# Sheet_Project_Batteries_V2.net
KiCad netlist of a schematic drawn in Altium Designer
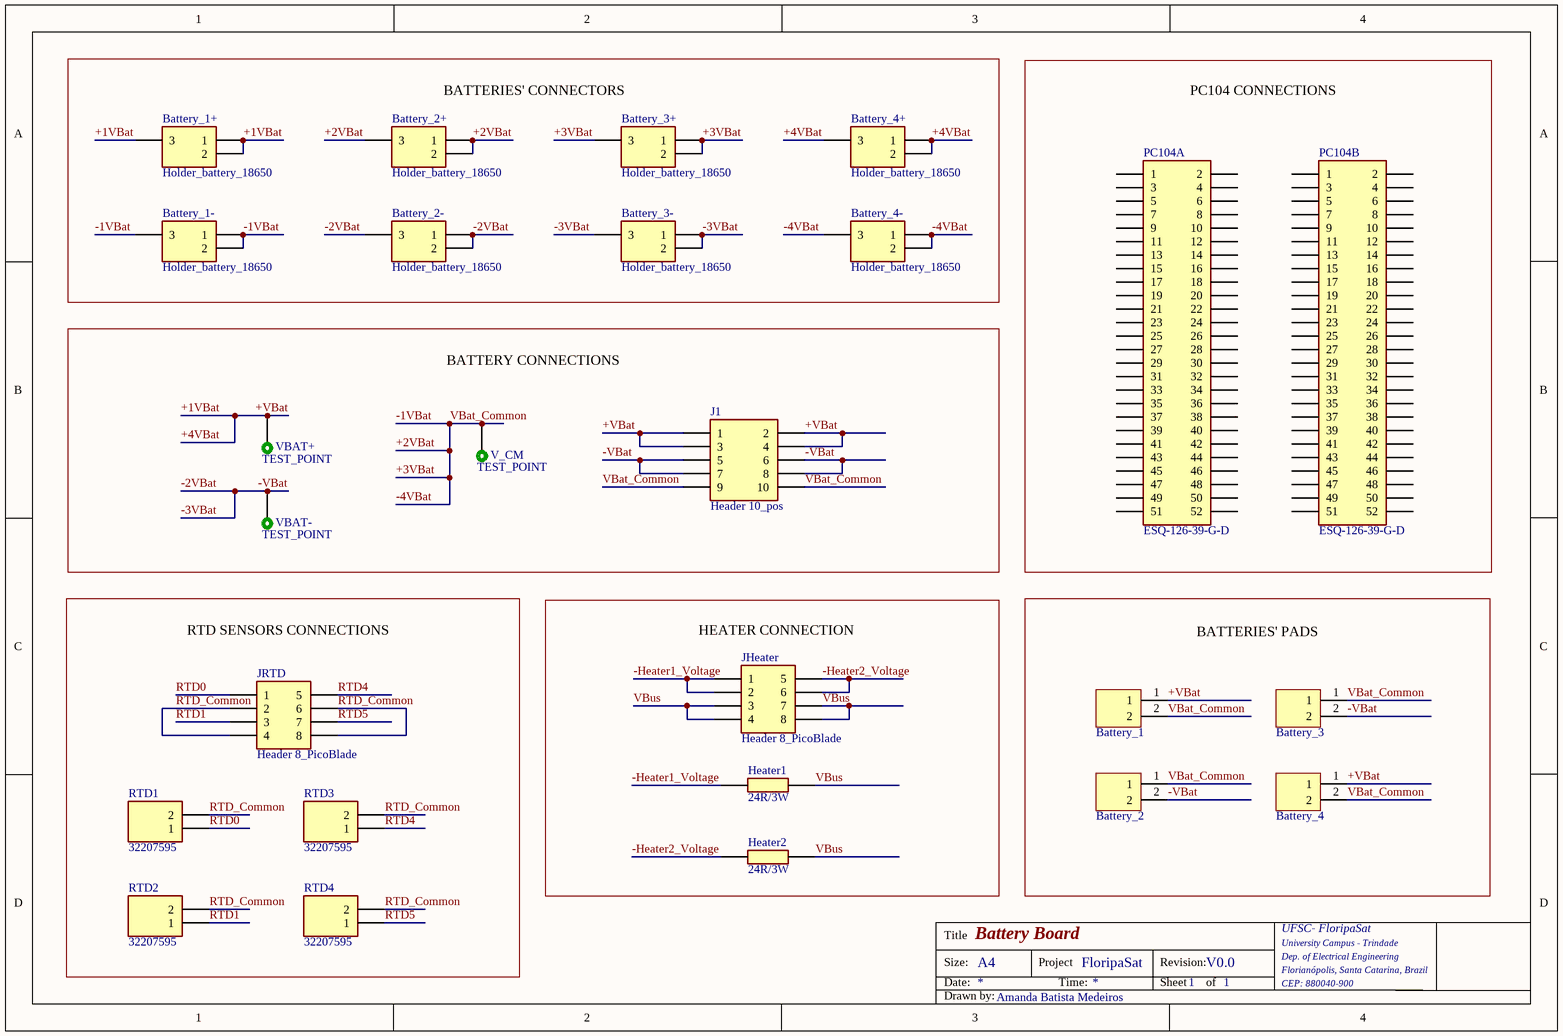
[diagram p0: Sheet_Project_Batteries_V2.SchDoc]

(export (version "E")
  (design (tool "Eeschema 10.0.6"))
  (components
    (comp (ref "Battery_1")
      (value "BATTERY")
      (footprint "BATTERY")
      (description "Battery Pads")
      (libsource (lib "Battery_V2") (part "BATTERY"))
    )
    (comp (ref "Battery_1+")
      (value "Holder_battery_18650")
      (footprint "54")
      (description "Cylindrical Battery Contacts, Clips, Holders & Springs 16-19mm PC BATTERY CLIP")
      (fields (field (name "MANUFACTURER_PART_NUMBER") "54") (field (name "MOUSER PART NUMBER") "534-54"))
      (libsource (lib "*") (part "54"))
    )
    (comp (ref "Battery_1-")
      (value "Holder_battery_18650")
      (footprint "54")
      (description "Cylindrical Battery Contacts, Clips, Holders & Springs 16-19mm PC BATTERY CLIP")
      (fields (field (name "MANUFACTURER_PART_NUMBER") "54") (field (name "MOUSER PART NUMBER") "534-54"))
      (libsource (lib "*") (part "54"))
    )
    (comp (ref "Battery_2")
      (value "BATTERY")
      (footprint "BATTERY")
      (description "Battery Pads")
      (libsource (lib "Battery_V2") (part "BATTERY"))
    )
    (comp (ref "Battery_2+")
      (value "Holder_battery_18650")
      (footprint "54")
      (description "Cylindrical Battery Contacts, Clips, Holders & Springs 16-19mm PC BATTERY CLIP")
      (fields (field (name "MANUFACTURER_PART_NUMBER") "54") (field (name "MOUSER PART NUMBER") "534-54"))
      (libsource (lib "*") (part "54"))
    )
    (comp (ref "Battery_2-")
      (value "Holder_battery_18650")
      (footprint "54")
      (description "Cylindrical Battery Contacts, Clips, Holders & Springs 16-19mm PC BATTERY CLIP")
      (fields (field (name "MANUFACTURER_PART_NUMBER") "54") (field (name "MOUSER PART NUMBER") "534-54"))
      (libsource (lib "*") (part "54"))
    )
    (comp (ref "Battery_3")
      (value "BATTERY")
      (footprint "BATTERY")
      (description "Battery Pads")
      (libsource (lib "Battery_V2") (part "BATTERY"))
    )
    (comp (ref "Battery_3+")
      (value "Holder_battery_18650")
      (footprint "54")
      (description "Cylindrical Battery Contacts, Clips, Holders & Springs 16-19mm PC BATTERY CLIP")
      (fields (field (name "MANUFACTURER_PART_NUMBER") "54") (field (name "MOUSER PART NUMBER") "534-54"))
      (libsource (lib "*") (part "54"))
    )
    (comp (ref "Battery_3-")
      (value "Holder_battery_18650")
      (footprint "54")
      (description "Cylindrical Battery Contacts, Clips, Holders & Springs 16-19mm PC BATTERY CLIP")
      (fields (field (name "MANUFACTURER_PART_NUMBER") "54") (field (name "MOUSER PART NUMBER") "534-54"))
      (libsource (lib "*") (part "54"))
    )
    (comp (ref "Battery_4")
      (value "BATTERY")
      (footprint "BATTERY")
      (description "Battery Pads")
      (libsource (lib "Battery_V2") (part "BATTERY"))
    )
    (comp (ref "Battery_4+")
      (value "Holder_battery_18650")
      (footprint "54")
      (description "Cylindrical Battery Contacts, Clips, Holders & Springs 16-19mm PC BATTERY CLIP")
      (fields (field (name "MANUFACTURER_PART_NUMBER") "54") (field (name "MOUSER PART NUMBER") "534-54"))
      (libsource (lib "*") (part "54"))
    )
    (comp (ref "Battery_4-")
      (value "Holder_battery_18650")
      (footprint "54")
      (description "Cylindrical Battery Contacts, Clips, Holders & Springs 16-19mm PC BATTERY CLIP")
      (fields (field (name "MANUFACTURER_PART_NUMBER") "54") (field (name "MOUSER PART NUMBER") "534-54"))
      (libsource (lib "*") (part "54"))
    )
    (comp (ref "Heater1")
      (value "24R/3W")
      (footprint "RESAD3322W86L1422D475")
      (description "Wirewound Resistors - Through Hole 3watts 24ohms 1%")
      (fields (field (name "MANUFACTURER_PART_NUMBER") "RS02B24R00FE12"))
      (libsource (lib "*") (part "RS02B24R00FE12"))
    )
    (comp (ref "Heater2")
      (value "24R/3W")
      (footprint "RESAD3322W86L1422D475")
      (description "Wirewound Resistors - Through Hole 3watts 24ohms 1%")
      (fields (field (name "MANUFACTURER_PART_NUMBER") "RS02B24R00FE12"))
      (libsource (lib "*") (part "RS02B24R00FE12"))
    )
    (comp (ref "J1")
      (value "Header 10_pos")
      (footprint "HDRV10W64P254_2X5_1270X502X521P")
      (description "Headers & Wire Housings .100\" Terminal Strip")
      (fields
        (field (name "MANUFACTURER_PART_NUMBER") "TSW-105-05-G-D")
        (field (name "MOUSER PART NUMBER") "200-TSW10505GD")
      )
      (libsource (lib "*") (part "TSW-105-05-G-D"))
    )
    (comp (ref "JHeater")
      (value "Header 8_PicoBlade")
      (footprint "53398-0871")
      (description "Headers & Wire Housings VERTICAL HDR SMT 8P")
      (fields
        (field (name "MOUSER2 PART NUMBER") "538-53398-0871")
        (field (name "MANUFACTURER_PART_NUMBER") "53398-0871")
      )
      (libsource (lib "*") (part "53398-0871"))
    )
    (comp (ref "JRTD")
      (value "Header 8_PicoBlade")
      (footprint "53398-0871")
      (description "Headers & Wire Housings VERTICAL HDR SMT 8P")
      (fields
        (field (name "MOUSER2 PART NUMBER") "538-53398-0871")
        (field (name "MANUFACTURER_PART_NUMBER") "53398-0871")
      )
      (libsource (lib "*") (part "53398-0871"))
    )
    (comp (ref "PC104A")
      (value "ESQ-126-39-G-D")
      (footprint "ESQ-126-Y-X-D")
      (description "PC / 104 Connectors .100\" PC/104 Elevated Socket Strip")
      (fields (field (name "MOUSER PART NUMBER") "200-ESQ12639GD") (field (name "RS PART NUMBER") "1595654"))
      (libsource (lib "*") (part "ESQ-126-39-G-D"))
    )
    (comp (ref "PC104B")
      (value "ESQ-126-39-G-D")
      (footprint "ESQ-126-Y-X-D")
      (description "PC / 104 Connectors .100\" PC/104 Elevated Socket Strip")
      (fields (field (name "MOUSER PART NUMBER") "200-ESQ12639GD") (field (name "RS PART NUMBER") "1595654"))
      (libsource (lib "*") (part "ESQ-126-39-G-D"))
    )
    (comp (ref "RTD1")
      (value "32207595")
      (footprint "THRMC3216X70N")
      (description "Board Mount Temperature Sensors SMD1206(V) Pt 1000 Class B -50 to +130C")
      (libsource (lib "*") (part "32207595"))
    )
    (comp (ref "RTD2")
      (value "32207595")
      (footprint "THRMC3216X70N")
      (description "Board Mount Temperature Sensors SMD1206(V) Pt 1000 Class B -50 to +130C")
      (libsource (lib "*") (part "32207595"))
    )
    (comp (ref "RTD3")
      (value "32207595")
      (footprint "THRMC3216X70N")
      (description "Board Mount Temperature Sensors SMD1206(V) Pt 1000 Class B -50 to +130C")
      (libsource (lib "*") (part "32207595"))
    )
    (comp (ref "RTD4")
      (value "32207595")
      (footprint "THRMC3216X70N")
      (description "Board Mount Temperature Sensors SMD1206(V) Pt 1000 Class B -50 to +130C")
      (libsource (lib "*") (part "32207595"))
    )
    (comp (ref "VBAT+")
      (value "TEST_POINT")
      (footprint "Test_Point")
      (description "Test Point - Headers & Wire Housings .100\" Terminal Strip")
      (libsource (lib "Battery_V2") (part "TEST_POINT"))
    )
    (comp (ref "VBAT-")
      (value "TEST_POINT")
      (footprint "Test_Point")
      (description "Test Point - Headers & Wire Housings .100\" Terminal Strip")
      (libsource (lib "Battery_V2") (part "TEST_POINT"))
    )
    (comp (ref "V_CM")
      (value "TEST_POINT")
      (footprint "Test_Point")
      (description "Test Point - Headers & Wire Housings .100\" Terminal Strip")
      (libsource (lib "Battery_V2") (part "TEST_POINT"))
    )
  )
  (nets
    (net (code "1") (name "/+1VBat") (class "Default")
      (node (ref "Battery_1") (pin "1") (pinfunction "1_1") (pintype "passive"))
      (node (ref "Battery_1+") (pin "1") (pinfunction "1_1") (pintype "passive"))
      (node (ref "Battery_1+") (pin "2") (pinfunction "2_2") (pintype "passive"))
      (node (ref "Battery_1+") (pin "3") (pinfunction "3_3") (pintype "passive"))
      (node (ref "Battery_4") (pin "1") (pinfunction "1_1") (pintype "passive"))
      (node (ref "Battery_4+") (pin "1") (pinfunction "1_1") (pintype "passive"))
      (node (ref "Battery_4+") (pin "2") (pinfunction "2_2") (pintype "passive"))
      (node (ref "Battery_4+") (pin "3") (pinfunction "3_3") (pintype "passive"))
      (node (ref "J1") (pin "1") (pinfunction "1_1") (pintype "passive"))
      (node (ref "J1") (pin "2") (pinfunction "2_2") (pintype "passive"))
      (node (ref "J1") (pin "3") (pinfunction "3_3") (pintype "passive"))
      (node (ref "J1") (pin "4") (pinfunction "4_4") (pintype "passive"))
      (node (ref "VBAT+") (pin "1") (pinfunction "1_1") (pintype "passive"))
    )
    (net (code "2") (name "/+2VBat") (class "Default")
      (node (ref "Battery_1") (pin "2") (pinfunction "2_2") (pintype "passive"))
      (node (ref "Battery_1-") (pin "1") (pinfunction "1_1") (pintype "passive"))
      (node (ref "Battery_1-") (pin "2") (pinfunction "2_2") (pintype "passive"))
      (node (ref "Battery_1-") (pin "3") (pinfunction "3_3") (pintype "passive"))
      (node (ref "Battery_2") (pin "1") (pinfunction "1_1") (pintype "passive"))
      (node (ref "Battery_2+") (pin "1") (pinfunction "1_1") (pintype "passive"))
      (node (ref "Battery_2+") (pin "2") (pinfunction "2_2") (pintype "passive"))
      (node (ref "Battery_2+") (pin "3") (pinfunction "3_3") (pintype "passive"))
      (node (ref "Battery_3") (pin "1") (pinfunction "1_1") (pintype "passive"))
      (node (ref "Battery_3+") (pin "1") (pinfunction "1_1") (pintype "passive"))
      (node (ref "Battery_3+") (pin "2") (pinfunction "2_2") (pintype "passive"))
      (node (ref "Battery_3+") (pin "3") (pinfunction "3_3") (pintype "passive"))
      (node (ref "Battery_4") (pin "2") (pinfunction "2_2") (pintype "passive"))
      (node (ref "Battery_4-") (pin "1") (pinfunction "1_1") (pintype "passive"))
      (node (ref "Battery_4-") (pin "2") (pinfunction "2_2") (pintype "passive"))
      (node (ref "Battery_4-") (pin "3") (pinfunction "3_3") (pintype "passive"))
      (node (ref "J1") (pin "10") (pinfunction "10_10") (pintype "passive"))
      (node (ref "J1") (pin "9") (pinfunction "9_9") (pintype "passive"))
      (node (ref "V_CM") (pin "1") (pinfunction "1_1") (pintype "passive"))
    )
    (net (code "3") (name "/-2VBat") (class "Default")
      (node (ref "Battery_2") (pin "2") (pinfunction "2_2") (pintype "passive"))
      (node (ref "Battery_2-") (pin "1") (pinfunction "1_1") (pintype "passive"))
      (node (ref "Battery_2-") (pin "2") (pinfunction "2_2") (pintype "passive"))
      (node (ref "Battery_2-") (pin "3") (pinfunction "3_3") (pintype "passive"))
      (node (ref "Battery_3") (pin "2") (pinfunction "2_2") (pintype "passive"))
      (node (ref "Battery_3-") (pin "1") (pinfunction "1_1") (pintype "passive"))
      (node (ref "Battery_3-") (pin "2") (pinfunction "2_2") (pintype "passive"))
      (node (ref "Battery_3-") (pin "3") (pinfunction "3_3") (pintype "passive"))
      (node (ref "J1") (pin "5") (pinfunction "5_5") (pintype "passive"))
      (node (ref "J1") (pin "6") (pinfunction "6_6") (pintype "passive"))
      (node (ref "J1") (pin "7") (pinfunction "7_7") (pintype "passive"))
      (node (ref "J1") (pin "8") (pinfunction "8_8") (pintype "passive"))
      (node (ref "VBAT-") (pin "1") (pinfunction "1_1") (pintype "passive"))
    )
    (net (code "4") (name "/-Heater1_Voltage") (class "Default")
      (node (ref "Heater1") (pin "1") (pinfunction "1_1") (pintype "passive"))
      (node (ref "JHeater") (pin "1") (pinfunction "1_1") (pintype "passive"))
      (node (ref "JHeater") (pin "2") (pinfunction "2_2") (pintype "passive"))
    )
    (net (code "5") (name "/-Heater2_Voltage") (class "Default")
      (node (ref "Heater2") (pin "1") (pinfunction "1_1") (pintype "passive"))
      (node (ref "JHeater") (pin "5") (pinfunction "5_5") (pintype "passive"))
      (node (ref "JHeater") (pin "6") (pinfunction "6_6") (pintype "passive"))
    )
    (net (code "6") (name "/RTD0") (class "Default")
      (node (ref "JRTD") (pin "1") (pinfunction "1_1") (pintype "passive"))
      (node (ref "RTD1") (pin "1") (pinfunction "1_1") (pintype "passive"))
    )
    (net (code "7") (name "/RTD1") (class "Default")
      (node (ref "JRTD") (pin "3") (pinfunction "3_3") (pintype "passive"))
      (node (ref "RTD2") (pin "1") (pinfunction "1_1") (pintype "passive"))
    )
    (net (code "8") (name "/RTD4") (class "Default")
      (node (ref "JRTD") (pin "5") (pinfunction "5_5") (pintype "passive"))
      (node (ref "RTD3") (pin "1") (pinfunction "1_1") (pintype "passive"))
    )
    (net (code "9") (name "/RTD5") (class "Default")
      (node (ref "JRTD") (pin "7") (pinfunction "7_7") (pintype "passive"))
      (node (ref "RTD4") (pin "1") (pinfunction "1_1") (pintype "passive"))
    )
    (net (code "10") (name "/RTD_Common") (class "Default")
      (node (ref "JRTD") (pin "2") (pinfunction "2_2") (pintype "passive"))
      (node (ref "JRTD") (pin "4") (pinfunction "4_4") (pintype "passive"))
      (node (ref "JRTD") (pin "6") (pinfunction "6_6") (pintype "passive"))
      (node (ref "JRTD") (pin "8") (pinfunction "8_8") (pintype "passive"))
      (node (ref "RTD1") (pin "2") (pinfunction "2_2") (pintype "passive"))
      (node (ref "RTD2") (pin "2") (pinfunction "2_2") (pintype "passive"))
      (node (ref "RTD3") (pin "2") (pinfunction "2_2") (pintype "passive"))
      (node (ref "RTD4") (pin "2") (pinfunction "2_2") (pintype "passive"))
    )
    (net (code "11") (name "/VBus") (class "Default")
      (node (ref "Heater1") (pin "2") (pinfunction "2_2") (pintype "passive"))
      (node (ref "Heater2") (pin "2") (pinfunction "2_2") (pintype "passive"))
      (node (ref "JHeater") (pin "3") (pinfunction "3_3") (pintype "passive"))
      (node (ref "JHeater") (pin "4") (pinfunction "4_4") (pintype "passive"))
      (node (ref "JHeater") (pin "7") (pinfunction "7_7") (pintype "passive"))
      (node (ref "JHeater") (pin "8") (pinfunction "8_8") (pintype "passive"))
    )
    (net (code "12") (name "unconnected-(PC104A-Pad1)") (class "Default")
      (node (ref "PC104A") (pin "1") (pinfunction "1_1") (pintype "passive"))
    )
    (net (code "13") (name "unconnected-(PC104A-Pad2)") (class "Default")
      (node (ref "PC104A") (pin "2") (pinfunction "2_2") (pintype "passive"))
    )
    (net (code "14") (name "unconnected-(PC104A-Pad3)") (class "Default")
      (node (ref "PC104A") (pin "3") (pinfunction "3_3") (pintype "passive"))
    )
    (net (code "15") (name "unconnected-(PC104A-Pad4)") (class "Default")
      (node (ref "PC104A") (pin "4") (pinfunction "4_4") (pintype "passive"))
    )
    (net (code "16") (name "unconnected-(PC104A-Pad5)") (class "Default")
      (node (ref "PC104A") (pin "5") (pinfunction "5_5") (pintype "passive"))
    )
    (net (code "17") (name "unconnected-(PC104A-Pad6)") (class "Default")
      (node (ref "PC104A") (pin "6") (pinfunction "6_6") (pintype "passive"))
    )
    (net (code "18") (name "unconnected-(PC104A-Pad7)") (class "Default")
      (node (ref "PC104A") (pin "7") (pinfunction "7_7") (pintype "passive"))
    )
    (net (code "19") (name "unconnected-(PC104A-Pad8)") (class "Default")
      (node (ref "PC104A") (pin "8") (pinfunction "8_8") (pintype "passive"))
    )
    (net (code "20") (name "unconnected-(PC104A-Pad9)") (class "Default")
      (node (ref "PC104A") (pin "9") (pinfunction "9_9") (pintype "passive"))
    )
    (net (code "21") (name "unconnected-(PC104A-Pad10)") (class "Default")
      (node (ref "PC104A") (pin "10") (pinfunction "10_10") (pintype "passive"))
    )
    (net (code "22") (name "unconnected-(PC104A-Pad11)") (class "Default")
      (node (ref "PC104A") (pin "11") (pinfunction "11_11") (pintype "passive"))
    )
    (net (code "23") (name "unconnected-(PC104A-Pad12)") (class "Default")
      (node (ref "PC104A") (pin "12") (pinfunction "12_12") (pintype "passive"))
    )
    (net (code "24") (name "unconnected-(PC104A-Pad13)") (class "Default")
      (node (ref "PC104A") (pin "13") (pinfunction "13_13") (pintype "passive"))
    )
    (net (code "25") (name "unconnected-(PC104A-Pad14)") (class "Default")
      (node (ref "PC104A") (pin "14") (pinfunction "14_14") (pintype "passive"))
    )
    (net (code "26") (name "unconnected-(PC104A-Pad15)") (class "Default")
      (node (ref "PC104A") (pin "15") (pinfunction "15_15") (pintype "passive"))
    )
    (net (code "27") (name "unconnected-(PC104A-Pad16)") (class "Default")
      (node (ref "PC104A") (pin "16") (pinfunction "16_16") (pintype "passive"))
    )
    (net (code "28") (name "unconnected-(PC104A-Pad17)") (class "Default")
      (node (ref "PC104A") (pin "17") (pinfunction "17_17") (pintype "passive"))
    )
    (net (code "29") (name "unconnected-(PC104A-Pad18)") (class "Default")
      (node (ref "PC104A") (pin "18") (pinfunction "18_18") (pintype "passive"))
    )
    (net (code "30") (name "unconnected-(PC104A-Pad19)") (class "Default")
      (node (ref "PC104A") (pin "19") (pinfunction "19_19") (pintype "passive"))
    )
    (net (code "31") (name "unconnected-(PC104A-Pad20)") (class "Default")
      (node (ref "PC104A") (pin "20") (pinfunction "20_20") (pintype "passive"))
    )
    (net (code "32") (name "unconnected-(PC104A-Pad21)") (class "Default")
      (node (ref "PC104A") (pin "21") (pinfunction "21_21") (pintype "passive"))
    )
    (net (code "33") (name "unconnected-(PC104A-Pad22)") (class "Default")
      (node (ref "PC104A") (pin "22") (pinfunction "22_22") (pintype "passive"))
    )
    (net (code "34") (name "unconnected-(PC104A-Pad23)") (class "Default")
      (node (ref "PC104A") (pin "23") (pinfunction "23_23") (pintype "passive"))
    )
    (net (code "35") (name "unconnected-(PC104A-Pad24)") (class "Default")
      (node (ref "PC104A") (pin "24") (pinfunction "24_24") (pintype "passive"))
    )
    (net (code "36") (name "unconnected-(PC104A-Pad25)") (class "Default")
      (node (ref "PC104A") (pin "25") (pinfunction "25_25") (pintype "passive"))
    )
    (net (code "37") (name "unconnected-(PC104A-Pad26)") (class "Default")
      (node (ref "PC104A") (pin "26") (pinfunction "26_26") (pintype "passive"))
    )
    (net (code "38") (name "unconnected-(PC104A-Pad27)") (class "Default")
      (node (ref "PC104A") (pin "27") (pinfunction "27_27") (pintype "passive"))
    )
    (net (code "39") (name "unconnected-(PC104A-Pad28)") (class "Default")
      (node (ref "PC104A") (pin "28") (pinfunction "28_28") (pintype "passive"))
    )
    (net (code "40") (name "unconnected-(PC104A-Pad29)") (class "Default")
      (node (ref "PC104A") (pin "29") (pinfunction "29_29") (pintype "passive"))
    )
    (net (code "41") (name "unconnected-(PC104A-Pad30)") (class "Default")
      (node (ref "PC104A") (pin "30") (pinfunction "30_30") (pintype "passive"))
    )
    (net (code "42") (name "unconnected-(PC104A-Pad31)") (class "Default")
      (node (ref "PC104A") (pin "31") (pinfunction "31_31") (pintype "passive"))
    )
    (net (code "43") (name "unconnected-(PC104A-Pad32)") (class "Default")
      (node (ref "PC104A") (pin "32") (pinfunction "32_32") (pintype "passive"))
    )
    (net (code "44") (name "unconnected-(PC104A-Pad33)") (class "Default")
      (node (ref "PC104A") (pin "33") (pinfunction "33_33") (pintype "passive"))
    )
    (net (code "45") (name "unconnected-(PC104A-Pad34)") (class "Default")
      (node (ref "PC104A") (pin "34") (pinfunction "34_34") (pintype "passive"))
    )
    (net (code "46") (name "unconnected-(PC104A-Pad35)") (class "Default")
      (node (ref "PC104A") (pin "35") (pinfunction "35_35") (pintype "passive"))
    )
    (net (code "47") (name "unconnected-(PC104A-Pad36)") (class "Default")
      (node (ref "PC104A") (pin "36") (pinfunction "36_36") (pintype "passive"))
    )
    (net (code "48") (name "unconnected-(PC104A-Pad37)") (class "Default")
      (node (ref "PC104A") (pin "37") (pinfunction "37_37") (pintype "passive"))
    )
    (net (code "49") (name "unconnected-(PC104A-Pad38)") (class "Default")
      (node (ref "PC104A") (pin "38") (pinfunction "38_38") (pintype "passive"))
    )
    (net (code "50") (name "unconnected-(PC104A-Pad39)") (class "Default")
      (node (ref "PC104A") (pin "39") (pinfunction "39_39") (pintype "passive"))
    )
    (net (code "51") (name "unconnected-(PC104A-Pad40)") (class "Default")
      (node (ref "PC104A") (pin "40") (pinfunction "40_40") (pintype "passive"))
    )
    (net (code "52") (name "unconnected-(PC104A-Pad41)") (class "Default")
      (node (ref "PC104A") (pin "41") (pinfunction "41_41") (pintype "passive"))
    )
    (net (code "53") (name "unconnected-(PC104A-Pad42)") (class "Default")
      (node (ref "PC104A") (pin "42") (pinfunction "42_42") (pintype "passive"))
    )
    (net (code "54") (name "unconnected-(PC104A-Pad43)") (class "Default")
      (node (ref "PC104A") (pin "43") (pinfunction "43_43") (pintype "passive"))
    )
    (net (code "55") (name "unconnected-(PC104A-Pad44)") (class "Default")
      (node (ref "PC104A") (pin "44") (pinfunction "44_44") (pintype "passive"))
    )
    (net (code "56") (name "unconnected-(PC104A-Pad45)") (class "Default")
      (node (ref "PC104A") (pin "45") (pinfunction "45_45") (pintype "passive"))
    )
    (net (code "57") (name "unconnected-(PC104A-Pad46)") (class "Default")
      (node (ref "PC104A") (pin "46") (pinfunction "46_46") (pintype "passive"))
    )
    (net (code "58") (name "unconnected-(PC104A-Pad47)") (class "Default")
      (node (ref "PC104A") (pin "47") (pinfunction "47_47") (pintype "passive"))
    )
    (net (code "59") (name "unconnected-(PC104A-Pad48)") (class "Default")
      (node (ref "PC104A") (pin "48") (pinfunction "48_48") (pintype "passive"))
    )
    (net (code "60") (name "unconnected-(PC104A-Pad49)") (class "Default")
      (node (ref "PC104A") (pin "49") (pinfunction "49_49") (pintype "passive"))
    )
    (net (code "61") (name "unconnected-(PC104A-Pad50)") (class "Default")
      (node (ref "PC104A") (pin "50") (pinfunction "50_50") (pintype "passive"))
    )
    (net (code "62") (name "unconnected-(PC104A-Pad51)") (class "Default")
      (node (ref "PC104A") (pin "51") (pinfunction "51_51") (pintype "passive"))
    )
    (net (code "63") (name "unconnected-(PC104A-Pad52)") (class "Default")
      (node (ref "PC104A") (pin "52") (pinfunction "52_52") (pintype "passive"))
    )
    (net (code "64") (name "unconnected-(PC104B-Pad1)") (class "Default")
      (node (ref "PC104B") (pin "1") (pinfunction "1_1") (pintype "passive"))
    )
    (net (code "65") (name "unconnected-(PC104B-Pad2)") (class "Default")
      (node (ref "PC104B") (pin "2") (pinfunction "2_2") (pintype "passive"))
    )
    (net (code "66") (name "unconnected-(PC104B-Pad3)") (class "Default")
      (node (ref "PC104B") (pin "3") (pinfunction "3_3") (pintype "passive"))
    )
    (net (code "67") (name "unconnected-(PC104B-Pad4)") (class "Default")
      (node (ref "PC104B") (pin "4") (pinfunction "4_4") (pintype "passive"))
    )
    (net (code "68") (name "unconnected-(PC104B-Pad5)") (class "Default")
      (node (ref "PC104B") (pin "5") (pinfunction "5_5") (pintype "passive"))
    )
    (net (code "69") (name "unconnected-(PC104B-Pad6)") (class "Default")
      (node (ref "PC104B") (pin "6") (pinfunction "6_6") (pintype "passive"))
    )
    (net (code "70") (name "unconnected-(PC104B-Pad7)") (class "Default")
      (node (ref "PC104B") (pin "7") (pinfunction "7_7") (pintype "passive"))
    )
    (net (code "71") (name "unconnected-(PC104B-Pad8)") (class "Default")
      (node (ref "PC104B") (pin "8") (pinfunction "8_8") (pintype "passive"))
    )
    (net (code "72") (name "unconnected-(PC104B-Pad9)") (class "Default")
      (node (ref "PC104B") (pin "9") (pinfunction "9_9") (pintype "passive"))
    )
    (net (code "73") (name "unconnected-(PC104B-Pad10)") (class "Default")
      (node (ref "PC104B") (pin "10") (pinfunction "10_10") (pintype "passive"))
    )
    (net (code "74") (name "unconnected-(PC104B-Pad11)") (class "Default")
      (node (ref "PC104B") (pin "11") (pinfunction "11_11") (pintype "passive"))
    )
    (net (code "75") (name "unconnected-(PC104B-Pad12)") (class "Default")
      (node (ref "PC104B") (pin "12") (pinfunction "12_12") (pintype "passive"))
    )
    (net (code "76") (name "unconnected-(PC104B-Pad13)") (class "Default")
      (node (ref "PC104B") (pin "13") (pinfunction "13_13") (pintype "passive"))
    )
    (net (code "77") (name "unconnected-(PC104B-Pad14)") (class "Default")
      (node (ref "PC104B") (pin "14") (pinfunction "14_14") (pintype "passive"))
    )
    (net (code "78") (name "unconnected-(PC104B-Pad15)") (class "Default")
      (node (ref "PC104B") (pin "15") (pinfunction "15_15") (pintype "passive"))
    )
    (net (code "79") (name "unconnected-(PC104B-Pad16)") (class "Default")
      (node (ref "PC104B") (pin "16") (pinfunction "16_16") (pintype "passive"))
    )
    (net (code "80") (name "unconnected-(PC104B-Pad17)") (class "Default")
      (node (ref "PC104B") (pin "17") (pinfunction "17_17") (pintype "passive"))
    )
    (net (code "81") (name "unconnected-(PC104B-Pad18)") (class "Default")
      (node (ref "PC104B") (pin "18") (pinfunction "18_18") (pintype "passive"))
    )
    (net (code "82") (name "unconnected-(PC104B-Pad19)") (class "Default")
      (node (ref "PC104B") (pin "19") (pinfunction "19_19") (pintype "passive"))
    )
    (net (code "83") (name "unconnected-(PC104B-Pad20)") (class "Default")
      (node (ref "PC104B") (pin "20") (pinfunction "20_20") (pintype "passive"))
    )
    (net (code "84") (name "unconnected-(PC104B-Pad21)") (class "Default")
      (node (ref "PC104B") (pin "21") (pinfunction "21_21") (pintype "passive"))
    )
    (net (code "85") (name "unconnected-(PC104B-Pad22)") (class "Default")
      (node (ref "PC104B") (pin "22") (pinfunction "22_22") (pintype "passive"))
    )
    (net (code "86") (name "unconnected-(PC104B-Pad23)") (class "Default")
      (node (ref "PC104B") (pin "23") (pinfunction "23_23") (pintype "passive"))
    )
    (net (code "87") (name "unconnected-(PC104B-Pad24)") (class "Default")
      (node (ref "PC104B") (pin "24") (pinfunction "24_24") (pintype "passive"))
    )
    (net (code "88") (name "unconnected-(PC104B-Pad25)") (class "Default")
      (node (ref "PC104B") (pin "25") (pinfunction "25_25") (pintype "passive"))
    )
    (net (code "89") (name "unconnected-(PC104B-Pad26)") (class "Default")
      (node (ref "PC104B") (pin "26") (pinfunction "26_26") (pintype "passive"))
    )
    (net (code "90") (name "unconnected-(PC104B-Pad27)") (class "Default")
      (node (ref "PC104B") (pin "27") (pinfunction "27_27") (pintype "passive"))
    )
    (net (code "91") (name "unconnected-(PC104B-Pad28)") (class "Default")
      (node (ref "PC104B") (pin "28") (pinfunction "28_28") (pintype "passive"))
    )
    (net (code "92") (name "unconnected-(PC104B-Pad29)") (class "Default")
      (node (ref "PC104B") (pin "29") (pinfunction "29_29") (pintype "passive"))
    )
    (net (code "93") (name "unconnected-(PC104B-Pad30)") (class "Default")
      (node (ref "PC104B") (pin "30") (pinfunction "30_30") (pintype "passive"))
    )
    (net (code "94") (name "unconnected-(PC104B-Pad31)") (class "Default")
      (node (ref "PC104B") (pin "31") (pinfunction "31_31") (pintype "passive"))
    )
    (net (code "95") (name "unconnected-(PC104B-Pad32)") (class "Default")
      (node (ref "PC104B") (pin "32") (pinfunction "32_32") (pintype "passive"))
    )
    (net (code "96") (name "unconnected-(PC104B-Pad33)") (class "Default")
      (node (ref "PC104B") (pin "33") (pinfunction "33_33") (pintype "passive"))
    )
    (net (code "97") (name "unconnected-(PC104B-Pad34)") (class "Default")
      (node (ref "PC104B") (pin "34") (pinfunction "34_34") (pintype "passive"))
    )
    (net (code "98") (name "unconnected-(PC104B-Pad35)") (class "Default")
      (node (ref "PC104B") (pin "35") (pinfunction "35_35") (pintype "passive"))
    )
    (net (code "99") (name "unconnected-(PC104B-Pad36)") (class "Default")
      (node (ref "PC104B") (pin "36") (pinfunction "36_36") (pintype "passive"))
    )
    (net (code "100") (name "unconnected-(PC104B-Pad37)") (class "Default")
      (node (ref "PC104B") (pin "37") (pinfunction "37_37") (pintype "passive"))
    )
    (net (code "101") (name "unconnected-(PC104B-Pad38)") (class "Default")
      (node (ref "PC104B") (pin "38") (pinfunction "38_38") (pintype "passive"))
    )
    (net (code "102") (name "unconnected-(PC104B-Pad39)") (class "Default")
      (node (ref "PC104B") (pin "39") (pinfunction "39_39") (pintype "passive"))
    )
    (net (code "103") (name "unconnected-(PC104B-Pad40)") (class "Default")
      (node (ref "PC104B") (pin "40") (pinfunction "40_40") (pintype "passive"))
    )
    (net (code "104") (name "unconnected-(PC104B-Pad41)") (class "Default")
      (node (ref "PC104B") (pin "41") (pinfunction "41_41") (pintype "passive"))
    )
    (net (code "105") (name "unconnected-(PC104B-Pad42)") (class "Default")
      (node (ref "PC104B") (pin "42") (pinfunction "42_42") (pintype "passive"))
    )
    (net (code "106") (name "unconnected-(PC104B-Pad43)") (class "Default")
      (node (ref "PC104B") (pin "43") (pinfunction "43_43") (pintype "passive"))
    )
    (net (code "107") (name "unconnected-(PC104B-Pad44)") (class "Default")
      (node (ref "PC104B") (pin "44") (pinfunction "44_44") (pintype "passive"))
    )
    (net (code "108") (name "unconnected-(PC104B-Pad45)") (class "Default")
      (node (ref "PC104B") (pin "45") (pinfunction "45_45") (pintype "passive"))
    )
    (net (code "109") (name "unconnected-(PC104B-Pad46)") (class "Default")
      (node (ref "PC104B") (pin "46") (pinfunction "46_46") (pintype "passive"))
    )
    (net (code "110") (name "unconnected-(PC104B-Pad47)") (class "Default")
      (node (ref "PC104B") (pin "47") (pinfunction "47_47") (pintype "passive"))
    )
    (net (code "111") (name "unconnected-(PC104B-Pad48)") (class "Default")
      (node (ref "PC104B") (pin "48") (pinfunction "48_48") (pintype "passive"))
    )
    (net (code "112") (name "unconnected-(PC104B-Pad49)") (class "Default")
      (node (ref "PC104B") (pin "49") (pinfunction "49_49") (pintype "passive"))
    )
    (net (code "113") (name "unconnected-(PC104B-Pad50)") (class "Default")
      (node (ref "PC104B") (pin "50") (pinfunction "50_50") (pintype "passive"))
    )
    (net (code "114") (name "unconnected-(PC104B-Pad51)") (class "Default")
      (node (ref "PC104B") (pin "51") (pinfunction "51_51") (pintype "passive"))
    )
    (net (code "115") (name "unconnected-(PC104B-Pad52)") (class "Default")
      (node (ref "PC104B") (pin "52") (pinfunction "52_52") (pintype "passive"))
    )
  )
)
